# Channel_One.net
KiCad netlist of a schematic drawn in Altium Designer
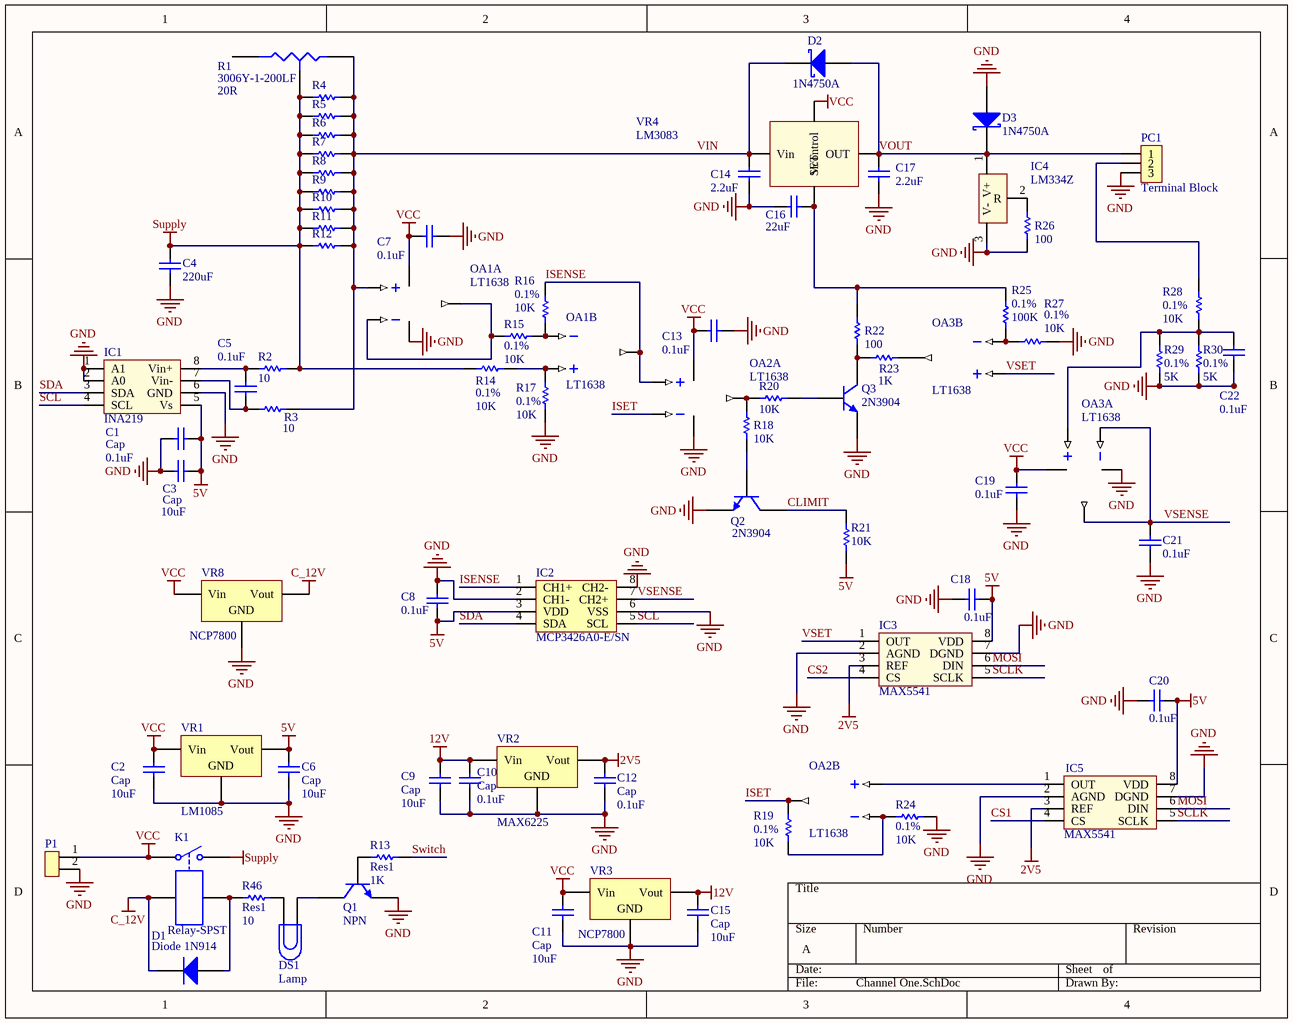
[diagram p0: Channel One.SchDoc]

(export (version "E")
  (design (tool "Eeschema 10.0.6"))
  (components
    (comp (ref "C1")
      (value "Cap")
      (footprint "RAD-0.1")
      (description "Capacitor")
      (fields (field (name "ALTIUM_VALUE") "0.1uF") (field (name "PUBLISHER") "Altium Limited"))
      (libsource (lib "Miscellaneous Devices") (part "Cap"))
    )
    (comp (ref "C2")
      (value "Cap")
      (footprint "RAD-0.2")
      (description "Capacitor")
      (fields (field (name "ALTIUM_VALUE") "10uF") (field (name "PUBLISHER") "Altium Limited"))
      (libsource (lib "Miscellaneous Devices") (part "Cap"))
    )
    (comp (ref "C3")
      (value "Cap")
      (footprint "RAD-0.2")
      (description "Capacitor")
      (fields (field (name "ALTIUM_VALUE") "10uF") (field (name "PUBLISHER") "Altium Limited"))
      (libsource (lib "Miscellaneous Devices") (part "Cap"))
    )
    (comp (ref "C4")
      (value "220uF")
      (footprint "RAD-0.2")
      (description "Capacitor")
      (fields (field (name "Comment") "Cap") (field (name "PUBLISHER") "Altium Limited"))
      (libsource (lib "Miscellaneous Devices") (part "Cap"))
    )
    (comp (ref "C5")
      (value "0.1uF")
      (footprint "RAD-0.1")
      (description "Capacitor")
      (fields (field (name "Comment") "Cap") (field (name "PUBLISHER") "Altium Limited"))
      (libsource (lib "Miscellaneous Devices") (part "Cap"))
    )
    (comp (ref "C6")
      (value "Cap")
      (footprint "RAD-0.2")
      (description "Capacitor")
      (fields (field (name "ALTIUM_VALUE") "10uF") (field (name "PUBLISHER") "Altium Limited"))
      (libsource (lib "Miscellaneous Devices") (part "Cap"))
    )
    (comp (ref "C7")
      (value "0.1uF")
      (footprint "RAD-0.1")
      (description "Capacitor")
      (fields (field (name "Comment") "Cap") (field (name "PUBLISHER") "Altium Limited"))
      (libsource (lib "Miscellaneous Devices") (part "Cap"))
    )
    (comp (ref "C8")
      (value "0.1uF")
      (footprint "RAD-0.1")
      (description "Capacitor")
      (fields (field (name "Comment") "Cap") (field (name "PUBLISHER") "Altium Limited"))
      (libsource (lib "Miscellaneous Devices") (part "Cap"))
    )
    (comp (ref "C9")
      (value "Cap")
      (footprint "RAD-0.2")
      (description "Capacitor")
      (fields (field (name "ALTIUM_VALUE") "10uF") (field (name "PUBLISHER") "Altium Limited"))
      (libsource (lib "Miscellaneous Devices") (part "Cap"))
    )
    (comp (ref "C10")
      (value "Cap")
      (footprint "RAD-0.1")
      (description "Capacitor")
      (fields (field (name "ALTIUM_VALUE") "0.1uF") (field (name "PUBLISHER") "Altium Limited"))
      (libsource (lib "Miscellaneous Devices") (part "Cap"))
    )
    (comp (ref "C11")
      (value "Cap")
      (footprint "RAD-0.2")
      (description "Capacitor")
      (fields (field (name "ALTIUM_VALUE") "10uF") (field (name "PUBLISHER") "Altium Limited"))
      (libsource (lib "Miscellaneous Devices") (part "Cap"))
    )
    (comp (ref "C12")
      (value "Cap")
      (footprint "RAD-0.1")
      (description "Capacitor")
      (fields (field (name "ALTIUM_VALUE") "0.1uF") (field (name "PUBLISHER") "Altium Limited"))
      (libsource (lib "Power Supply Library") (part "Cap"))
    )
    (comp (ref "C13")
      (value "0.1uF")
      (footprint "RAD-0.1")
      (description "Capacitor")
      (fields (field (name "Comment") "Cap") (field (name "PUBLISHER") "Altium Limited"))
      (libsource (lib "Miscellaneous Devices") (part "Cap"))
    )
    (comp (ref "C14")
      (value "2.2uF")
      (footprint "RAD-0.1")
      (description "Capacitor")
      (fields (field (name "Comment") "Cap") (field (name "PUBLISHER") "Altium Limited"))
      (libsource (lib "Miscellaneous Devices") (part "Cap"))
    )
    (comp (ref "C15")
      (value "Cap")
      (footprint "RAD-0.2")
      (description "Capacitor")
      (fields (field (name "ALTIUM_VALUE") "10uF") (field (name "PUBLISHER") "Altium Limited"))
      (libsource (lib "Miscellaneous Devices") (part "Cap"))
    )
    (comp (ref "C16")
      (value "22uF")
      (footprint "RAD-0.2")
      (description "Capacitor")
      (fields (field (name "Comment") "Cap") (field (name "PUBLISHER") "Altium Limited"))
      (libsource (lib "Miscellaneous Devices") (part "Cap"))
    )
    (comp (ref "C17")
      (value "2.2uF")
      (footprint "RAD-0.2")
      (description "Capacitor")
      (fields (field (name "Comment") "Cap") (field (name "PUBLISHER") "Altium Limited"))
      (libsource (lib "Miscellaneous Devices") (part "Cap"))
    )
    (comp (ref "C18")
      (value "0.1uF")
      (footprint "RAD-0.1")
      (description "Capacitor")
      (fields (field (name "Comment") "Cap") (field (name "PUBLISHER") "Altium Limited"))
      (libsource (lib "Miscellaneous Devices") (part "Cap"))
    )
    (comp (ref "C19")
      (value "0.1uF")
      (footprint "RAD-0.1")
      (description "Capacitor")
      (fields (field (name "Comment") "Cap") (field (name "PUBLISHER") "Altium Limited"))
      (libsource (lib "Miscellaneous Devices") (part "Cap"))
    )
    (comp (ref "C20")
      (value "0.1uF")
      (footprint "RAD-0.1")
      (description "Capacitor")
      (fields (field (name "Comment") "Cap") (field (name "PUBLISHER") "Altium Limited"))
      (libsource (lib "Miscellaneous Devices") (part "Cap"))
    )
    (comp (ref "C21")
      (value "0.1uF")
      (footprint "RAD-0.1")
      (description "Capacitor")
      (fields (field (name "Comment") "Cap") (field (name "PUBLISHER") "Altium Limited"))
      (libsource (lib "Miscellaneous Devices") (part "Cap"))
    )
    (comp (ref "C22")
      (value "0.1uF")
      (footprint "RAD-0.1")
      (description "Capacitor")
      (fields (field (name "Comment") "Cap") (field (name "PUBLISHER") "Altium Limited"))
      (libsource (lib "Miscellaneous Devices") (part "Cap"))
    )
    (comp (ref "D1")
      (value "Diode 1N914")
      (footprint "DO-35")
      (description "High Conductance Fast Diode")
      (fields (field (name "PUBLISHER") "Altium Limited"))
      (libsource (lib "Miscellaneous Devices") (part "Diode 1N914"))
    )
    (comp (ref "D2")
      (value "1N4750A")
      (footprint "DO-35")
      (description "Schottky Diode")
      (fields (field (name "PUBLISHER") "Altium Limited"))
      (libsource (lib "Miscellaneous Devices") (part "D Schottky"))
    )
    (comp (ref "D3")
      (value "1N4750A")
      (footprint "DO-35")
      (description "Schottky Diode")
      (fields (field (name "PUBLISHER") "Altium Limited"))
      (libsource (lib "Miscellaneous Devices") (part "D Schottky"))
    )
    (comp (ref "DS1")
      (value "Lamp")
      (footprint "PIN2")
      (description "Incandescent Bulb")
      (fields (field (name "PUBLISHER") "Altium Limited"))
      (libsource (lib "Miscellaneous Devices") (part "Lamp"))
    )
    (comp (ref "IC1")
      (value "INA219")
      (footprint "8-SO")
      (libsource (lib "Power Supply Library") (part "Current Sense"))
    )
    (comp (ref "IC2")
      (value "MCP3426A0-E/SN")
      (footprint "8-SO")
      (libsource (lib "Power Supply Library") (part "ADC"))
    )
    (comp (ref "IC3")
      (value "MAX5541")
      (footprint "8-SO")
      (libsource (lib "Power Supply Library") (part "DAC"))
    )
    (comp (ref "IC4")
      (value "LM334Z")
      (footprint "LM134")
      (libsource (lib "Power Supply Library") (part "Constant Current"))
    )
    (comp (ref "IC5")
      (value "MAX5541")
      (footprint "8-SO")
      (libsource (lib "Power Supply Library") (part "DAC"))
    )
    (comp (ref "K1")
      (value "Relay-SPST")
      (footprint "MODULE4")
      (description "Single-Pole Single-Throw Relay")
      (fields (field (name "PUBLISHER") "Altium Limited"))
      (libsource (lib "Power Supply Library") (part "Relay-SPST"))
    )
    (comp (ref "OA1")
      (value "LT1638")
      (footprint "8-DIP")
      (libsource (lib "Power Supply Library") (part "Operational Amp"))
    )
    (comp (ref "OA2")
      (value "LT1638")
      (footprint "8-DIP")
      (libsource (lib "Power Supply Library") (part "Operational Amp"))
    )
    (comp (ref "OA3")
      (value "LT1638")
      (footprint "8-DIP")
      (libsource (lib "Power Supply Library") (part "Operational Amp"))
    )
    (comp (ref "P1")
      (value "Power Connector")
      (footprint "Power Connector")
      (libsource (lib "Power Supply Library") (part "Power Connector"))
    )
    (comp (ref "PC1")
      (value "Terminal Block")
      (footprint "Terminal Block 3")
      (libsource (lib "Power Supply Library") (part "Terminal Block"))
    )
    (comp (ref "Q1")
      (value "NPN")
      (footprint "TO-226-AA")
      (description "NPN Bipolar Transistor")
      (fields (field (name "PUBLISHER") "Altium Limited"))
      (libsource (lib "Power Supply Library") (part "NPN"))
    )
    (comp (ref "Q2")
      (value "2N3904")
      (footprint "TO-226-AA")
      (description "NPN Bipolar Transistor")
      (fields (field (name "PUBLISHER") "Altium Limited"))
      (libsource (lib "Miscellaneous Devices") (part "NPN"))
    )
    (comp (ref "Q3")
      (value "2N3904")
      (footprint "TO-226-AA")
      (description "NPN Bipolar Transistor")
      (fields (field (name "PUBLISHER") "Altium Limited"))
      (libsource (lib "Miscellaneous Devices") (part "NPN"))
    )
    (comp (ref "R1")
      (value "3006Y-1-200LF")
      (footprint "VR3")
      (description "Tapped Resistor")
      (fields (field (name "ALTIUM_VALUE") "20R") (field (name "PUBLISHER") "Altium Limited"))
      (libsource (lib "Power Supply Library") (part "Res Tap"))
    )
    (comp (ref "R2")
      (value "10")
      (footprint "AXIAL-0.3")
      (description "Resistor")
      (fields (field (name "Comment") "Res1") (field (name "PUBLISHER") "Altium Limited"))
      (libsource (lib "Miscellaneous Devices") (part "Res1"))
    )
    (comp (ref "R3")
      (value "10")
      (footprint "AXIAL-0.3")
      (description "Resistor")
      (fields (field (name "Comment") "Res1") (field (name "PUBLISHER") "Altium Limited"))
      (libsource (lib "Miscellaneous Devices") (part "Res1"))
    )
    (comp (ref "R4")
      (value "Shunt")
      (footprint "AXIAL-0.3")
      (description "Resistor")
      (fields (field (name "PUBLISHER") "Altium Limited"))
      (libsource (lib "Miscellaneous Devices") (part "Res1"))
    )
    (comp (ref "R5")
      (value "Shunt")
      (footprint "AXIAL-0.3")
      (description "Resistor")
      (fields (field (name "PUBLISHER") "Altium Limited"))
      (libsource (lib "Miscellaneous Devices") (part "Res1"))
    )
    (comp (ref "R6")
      (value "Shunt")
      (footprint "AXIAL-0.3")
      (description "Resistor")
      (fields (field (name "PUBLISHER") "Altium Limited"))
      (libsource (lib "Miscellaneous Devices") (part "Res1"))
    )
    (comp (ref "R7")
      (value "Shunt")
      (footprint "AXIAL-0.3")
      (description "Resistor")
      (fields (field (name "PUBLISHER") "Altium Limited"))
      (libsource (lib "Miscellaneous Devices") (part "Res1"))
    )
    (comp (ref "R8")
      (value "Shunt")
      (footprint "AXIAL-0.3")
      (description "Resistor")
      (fields (field (name "PUBLISHER") "Altium Limited"))
      (libsource (lib "Miscellaneous Devices") (part "Res1"))
    )
    (comp (ref "R9")
      (value "Shunt")
      (footprint "AXIAL-0.3")
      (description "Resistor")
      (fields (field (name "PUBLISHER") "Altium Limited"))
      (libsource (lib "Miscellaneous Devices") (part "Res1"))
    )
    (comp (ref "R10")
      (value "Shunt")
      (footprint "AXIAL-0.3")
      (description "Resistor")
      (fields (field (name "PUBLISHER") "Altium Limited"))
      (libsource (lib "Miscellaneous Devices") (part "Res1"))
    )
    (comp (ref "R11")
      (value "Shunt")
      (footprint "AXIAL-0.3")
      (description "Resistor")
      (fields (field (name "PUBLISHER") "Altium Limited"))
      (libsource (lib "Miscellaneous Devices") (part "Res1"))
    )
    (comp (ref "R12")
      (value "Shunt")
      (footprint "AXIAL-0.3")
      (description "Resistor")
      (fields (field (name "PUBLISHER") "Altium Limited"))
      (libsource (lib "Miscellaneous Devices") (part "Res1"))
    )
    (comp (ref "R13")
      (value "Res1")
      (footprint "AXIAL-0.3")
      (description "Resistor")
      (fields (field (name "ALTIUM_VALUE") "1K") (field (name "PUBLISHER") "Altium Limited"))
      (libsource (lib "Power Supply Library") (part "Res1"))
    )
    (comp (ref "R14")
      (value "0.1%")
      (footprint "AXIAL-0.3")
      (description "Resistor")
      (fields (field (name "ALTIUM_VALUE") "10K") (field (name "PUBLISHER") "Altium Limited"))
      (libsource (lib "Miscellaneous Devices") (part "Res1"))
    )
    (comp (ref "R15")
      (value "0.1%")
      (footprint "AXIAL-0.3")
      (description "Resistor")
      (fields (field (name "ALTIUM_VALUE") "10K") (field (name "PUBLISHER") "Altium Limited"))
      (libsource (lib "Miscellaneous Devices") (part "Res1"))
    )
    (comp (ref "R16")
      (value "0.1%")
      (footprint "AXIAL-0.3")
      (description "Resistor")
      (fields (field (name "ALTIUM_VALUE") "10K") (field (name "PUBLISHER") "Altium Limited"))
      (libsource (lib "Miscellaneous Devices") (part "Res1"))
    )
    (comp (ref "R17")
      (value "0.1%")
      (footprint "AXIAL-0.3")
      (description "Resistor")
      (fields (field (name "ALTIUM_VALUE") "10K") (field (name "PUBLISHER") "Altium Limited"))
      (libsource (lib "Miscellaneous Devices") (part "Res1"))
    )
    (comp (ref "R18")
      (value "10K")
      (footprint "AXIAL-0.3")
      (description "Resistor")
      (fields (field (name "Comment") "Res") (field (name "PUBLISHER") "Altium Limited"))
      (libsource (lib "Miscellaneous Devices") (part "Res1"))
    )
    (comp (ref "R19")
      (value "0.1%")
      (footprint "AXIAL-0.3")
      (description "Resistor")
      (fields (field (name "ALTIUM_VALUE") "10K") (field (name "PUBLISHER") "Altium Limited"))
      (libsource (lib "Miscellaneous Devices") (part "Res1"))
    )
    (comp (ref "R20")
      (value "10K")
      (footprint "AXIAL-0.3")
      (description "Resistor")
      (fields (field (name "Comment") "Res") (field (name "PUBLISHER") "Altium Limited"))
      (libsource (lib "Miscellaneous Devices") (part "Res1"))
    )
    (comp (ref "R21")
      (value "10K")
      (footprint "AXIAL-0.3")
      (description "Resistor")
      (fields (field (name "Comment") "Res1") (field (name "PUBLISHER") "Altium Limited"))
      (libsource (lib "Miscellaneous Devices") (part "Res1"))
    )
    (comp (ref "R22")
      (value "100")
      (footprint "AXIAL-0.3")
      (description "Resistor")
      (fields (field (name "Comment") "Res") (field (name "PUBLISHER") "Altium Limited"))
      (libsource (lib "Miscellaneous Devices") (part "Res1"))
    )
    (comp (ref "R23")
      (value "1K")
      (footprint "AXIAL-0.3")
      (description "Resistor")
      (fields (field (name "Comment") "Res") (field (name "PUBLISHER") "Altium Limited"))
      (libsource (lib "Miscellaneous Devices") (part "Res1"))
    )
    (comp (ref "R24")
      (value "0.1%")
      (footprint "AXIAL-0.3")
      (description "Resistor")
      (fields (field (name "ALTIUM_VALUE") "10K") (field (name "PUBLISHER") "Altium Limited"))
      (libsource (lib "Miscellaneous Devices") (part "Res1"))
    )
    (comp (ref "R25")
      (value "0.1%")
      (footprint "AXIAL-0.3")
      (description "Resistor")
      (fields (field (name "ALTIUM_VALUE") "100K") (field (name "PUBLISHER") "Altium Limited"))
      (libsource (lib "Miscellaneous Devices") (part "Res1"))
    )
    (comp (ref "R26")
      (value "100")
      (footprint "AXIAL-0.3")
      (description "Resistor")
      (fields (field (name "Comment") "Res") (field (name "PUBLISHER") "Altium Limited"))
      (libsource (lib "Miscellaneous Devices") (part "Res1"))
    )
    (comp (ref "R27")
      (value "0.1%")
      (footprint "AXIAL-0.3")
      (description "Resistor")
      (fields (field (name "ALTIUM_VALUE") "10K") (field (name "PUBLISHER") "Altium Limited"))
      (libsource (lib "Miscellaneous Devices") (part "Res1"))
    )
    (comp (ref "R28")
      (value "0.1%")
      (footprint "AXIAL-0.3")
      (description "Resistor")
      (fields (field (name "ALTIUM_VALUE") "10K") (field (name "PUBLISHER") "Altium Limited"))
      (libsource (lib "Miscellaneous Devices") (part "Res1"))
    )
    (comp (ref "R29")
      (value "0.1%")
      (footprint "AXIAL-0.3")
      (description "Resistor")
      (fields (field (name "ALTIUM_VALUE") "5K") (field (name "PUBLISHER") "Altium Limited"))
      (libsource (lib "Miscellaneous Devices") (part "Res1"))
    )
    (comp (ref "R30")
      (value "0.1%")
      (footprint "AXIAL-0.3")
      (description "Resistor")
      (fields (field (name "ALTIUM_VALUE") "5K") (field (name "PUBLISHER") "Altium Limited"))
      (libsource (lib "Miscellaneous Devices") (part "Res1"))
    )
    (comp (ref "R46")
      (value "Res1")
      (footprint "AXIAL-0.3")
      (description "Resistor")
      (fields (field (name "ALTIUM_VALUE") "10") (field (name "PUBLISHER") "Altium Limited"))
      (libsource (lib "Power Supply Library") (part "Res1"))
    )
    (comp (ref "VR1")
      (value "LM1085")
      (footprint "TO220")
      (libsource (lib "Power Supply Library") (part "Voltage Regulator 5V"))
    )
    (comp (ref "VR2")
      (value "MAX6225")
      (footprint "8-DIP")
      (libsource (lib "Power Supply Library") (part "Voltage Reference 2.5V"))
    )
    (comp (ref "VR3")
      (value "NCP7800")
      (footprint "TO220")
      (libsource (lib "Power Supply Library") (part "Voltage Regulator 12V"))
    )
    (comp (ref "VR4")
      (value "LM3083")
      (footprint "LT3083")
      (libsource (lib "Power Supply Library") (part "Adjustable Regulator"))
    )
    (comp (ref "VR8")
      (value "NCP7800")
      (footprint "TO220")
      (libsource (lib "Power Supply Library") (part "Voltage Regulator 12V"))
    )
  )
  (nets
    (net (code "1") (name "/CLIMIT") (class "Default")
      (node (ref "Q2") (pin "1") (pinfunction "C_1") (pintype "passive"))
      (node (ref "R21") (pin "2") (pinfunction "2_2") (pintype "passive"))
    )
    (net (code "2") (name "/CS1") (class "Default")
      (node (ref "IC5") (pin "4") (pinfunction "CS_4") (pintype "passive"))
    )
    (net (code "3") (name "/CS2") (class "Default")
      (node (ref "IC3") (pin "4") (pinfunction "CS_4") (pintype "passive"))
    )
    (net (code "4") (name "/ISENSE") (class "Default")
      (node (ref "IC2") (pin "1") (pinfunction "CH1+_1") (pintype "passive"))
      (node (ref "OA1") (pin "7") (pinfunction "OUTB_7") (pintype "output"))
      (node (ref "OA2") (pin "3") (pinfunction "+INA_3") (pintype "input"))
      (node (ref "R16") (pin "2") (pinfunction "2_2") (pintype "passive"))
    )
    (net (code "5") (name "/ISET") (class "Default")
      (node (ref "OA2") (pin "2") (pinfunction "-INA_2") (pintype "input"))
      (node (ref "OA2") (pin "7") (pinfunction "OUTB_7") (pintype "output"))
      (node (ref "R19") (pin "1") (pinfunction "1_1") (pintype "passive"))
    )
    (net (code "6") (name "/MOSI") (class "Default")
      (node (ref "IC3") (pin "6") (pinfunction "DIN_6") (pintype "passive"))
      (node (ref "IC5") (pin "6") (pinfunction "DIN_6") (pintype "passive"))
    )
    (net (code "7") (name "/SCL") (class "Default")
      (node (ref "IC1") (pin "4") (pinfunction "SCL_4") (pintype "passive"))
      (node (ref "IC2") (pin "5") (pinfunction "SCL_5") (pintype "passive"))
    )
    (net (code "8") (name "/SCLK") (class "Default")
      (node (ref "IC3") (pin "5") (pinfunction "SCLK_5") (pintype "passive"))
      (node (ref "IC5") (pin "5") (pinfunction "SCLK_5") (pintype "passive"))
    )
    (net (code "9") (name "/SDA") (class "Default")
      (node (ref "IC1") (pin "3") (pinfunction "SDA_3") (pintype "passive"))
      (node (ref "IC2") (pin "4") (pinfunction "SDA_4") (pintype "passive"))
    )
    (net (code "10") (name "/Switch") (class "Default")
      (node (ref "R13") (pin "1") (pinfunction "1_1") (pintype "passive"))
    )
    (net (code "11") (name "/VIN") (class "Default")
      (node (ref "C14") (pin "2") (pinfunction "2_2") (pintype "passive"))
      (node (ref "D2") (pin "2") (pinfunction "K_2") (pintype "passive"))
      (node (ref "OA1") (pin "3") (pinfunction "+INA_3") (pintype "input"))
      (node (ref "R1") (pin "1") (pinfunction "A_1") (pintype "passive"))
      (node (ref "R10") (pin "2") (pinfunction "2_2") (pintype "passive"))
      (node (ref "R11") (pin "2") (pinfunction "2_2") (pintype "passive"))
      (node (ref "R12") (pin "2") (pinfunction "2_2") (pintype "passive"))
      (node (ref "R3") (pin "2") (pinfunction "2_2") (pintype "passive"))
      (node (ref "R4") (pin "2") (pinfunction "2_2") (pintype "passive"))
      (node (ref "R5") (pin "2") (pinfunction "2_2") (pintype "passive"))
      (node (ref "R6") (pin "2") (pinfunction "2_2") (pintype "passive"))
      (node (ref "R7") (pin "2") (pinfunction "2_2") (pintype "passive"))
      (node (ref "R8") (pin "2") (pinfunction "2_2") (pintype "passive"))
      (node (ref "R9") (pin "2") (pinfunction "2_2") (pintype "passive"))
      (node (ref "VR4") (pin "5") (pinfunction "Vin_5") (pintype "passive"))
    )
    (net (code "12") (name "/VOUT") (class "Default")
      (node (ref "C17") (pin "2") (pinfunction "2_2") (pintype "passive"))
      (node (ref "D2") (pin "1") (pinfunction "A_1") (pintype "passive"))
      (node (ref "D3") (pin "2") (pinfunction "K_2") (pintype "passive"))
      (node (ref "IC4") (pin "1") (pinfunction "V+_1") (pintype "passive"))
      (node (ref "PC1") (pin "1") (pinfunction "1_1") (pintype "passive"))
      (node (ref "VR4") (pin "3") (pinfunction "OUT_3") (pintype "passive"))
    )
    (net (code "13") (name "/VSENSE") (class "Default")
      (node (ref "C21") (pin "1") (pinfunction "1_1") (pintype "passive"))
      (node (ref "IC2") (pin "7") (pinfunction "CH2+_7") (pintype "passive"))
      (node (ref "OA3") (pin "1") (pinfunction "OUTA_1") (pintype "output"))
      (node (ref "OA3") (pin "2") (pinfunction "-INA_2") (pintype "input"))
    )
    (net (code "14") (name "/VSET") (class "Default")
      (node (ref "IC3") (pin "1") (pinfunction "OUT_1") (pintype "passive"))
      (node (ref "OA3") (pin "5") (pinfunction "+INB_5") (pintype "input"))
    )
    (net (code "15") (name "2V5") (class "Default")
      (node (ref "C12") (pin "2") (pinfunction "2_2") (pintype "passive"))
      (node (ref "IC3") (pin "3") (pinfunction "REF_3") (pintype "passive"))
      (node (ref "IC5") (pin "3") (pinfunction "REF_3") (pintype "passive"))
      (node (ref "VR2") (pin "6") (pinfunction "Vout_6") (pintype "passive"))
    )
    (net (code "16") (name "5V") (class "Default")
      (node (ref "C1") (pin "2") (pinfunction "2_2") (pintype "passive"))
      (node (ref "C18") (pin "2") (pinfunction "2_2") (pintype "passive"))
      (node (ref "C20") (pin "2") (pinfunction "2_2") (pintype "passive"))
      (node (ref "C3") (pin "2") (pinfunction "2_2") (pintype "passive"))
      (node (ref "C6") (pin "2") (pinfunction "2_2") (pintype "passive"))
      (node (ref "C8") (pin "1") (pinfunction "1_1") (pintype "passive"))
      (node (ref "IC1") (pin "5") (pinfunction "Vs_5") (pintype "passive"))
      (node (ref "IC2") (pin "3") (pinfunction "VDD_3") (pintype "passive"))
      (node (ref "IC3") (pin "8") (pinfunction "VDD_8") (pintype "passive"))
      (node (ref "IC5") (pin "8") (pinfunction "VDD_8") (pintype "passive"))
      (node (ref "R21") (pin "1") (pinfunction "1_1") (pintype "passive"))
      (node (ref "VR1") (pin "3") (pinfunction "Vout_3") (pintype "passive"))
    )
    (net (code "17") (name "12V") (class "Default")
      (node (ref "C10") (pin "2") (pinfunction "2_2") (pintype "passive"))
      (node (ref "C15") (pin "2") (pinfunction "2_2") (pintype "passive"))
      (node (ref "C9") (pin "2") (pinfunction "2_2") (pintype "passive"))
      (node (ref "VR2") (pin "2") (pinfunction "Vin_2") (pintype "passive"))
      (node (ref "VR3") (pin "3") (pinfunction "Vout_3") (pintype "passive"))
    )
    (net (code "18") (name "C_12V") (class "Default")
      (node (ref "D1") (pin "2") (pinfunction "K_2") (pintype "passive"))
      (node (ref "K1") (pin "3") (pinfunction "3_3") (pintype "passive"))
      (node (ref "VR8") (pin "3") (pinfunction "Vout_3") (pintype "passive"))
    )
    (net (code "19") (name "GND") (class "Default")
      (node (ref "C1") (pin "1") (pinfunction "1_1") (pintype "passive"))
      (node (ref "C10") (pin "1") (pinfunction "1_1") (pintype "passive"))
      (node (ref "C11") (pin "1") (pinfunction "1_1") (pintype "passive"))
      (node (ref "C12") (pin "1") (pinfunction "1_1") (pintype "passive"))
      (node (ref "C13") (pin "2") (pinfunction "2_2") (pintype "passive"))
      (node (ref "C14") (pin "1") (pinfunction "1_1") (pintype "passive"))
      (node (ref "C15") (pin "1") (pinfunction "1_1") (pintype "passive"))
      (node (ref "C16") (pin "2") (pinfunction "2_2") (pintype "passive"))
      (node (ref "C17") (pin "1") (pinfunction "1_1") (pintype "passive"))
      (node (ref "C18") (pin "1") (pinfunction "1_1") (pintype "passive"))
      (node (ref "C19") (pin "1") (pinfunction "1_1") (pintype "passive"))
      (node (ref "C2") (pin "1") (pinfunction "1_1") (pintype "passive"))
      (node (ref "C20") (pin "1") (pinfunction "1_1") (pintype "passive"))
      (node (ref "C21") (pin "2") (pinfunction "2_2") (pintype "passive"))
      (node (ref "C22") (pin "2") (pinfunction "2_2") (pintype "passive"))
      (node (ref "C3") (pin "1") (pinfunction "1_1") (pintype "passive"))
      (node (ref "C4") (pin "1") (pinfunction "1_1") (pintype "passive"))
      (node (ref "C6") (pin "1") (pinfunction "1_1") (pintype "passive"))
      (node (ref "C7") (pin "2") (pinfunction "2_2") (pintype "passive"))
      (node (ref "C8") (pin "2") (pinfunction "2_2") (pintype "passive"))
      (node (ref "C9") (pin "1") (pinfunction "1_1") (pintype "passive"))
      (node (ref "D3") (pin "1") (pinfunction "A_1") (pintype "passive"))
      (node (ref "IC1") (pin "1") (pinfunction "A1_1") (pintype "passive"))
      (node (ref "IC1") (pin "2") (pinfunction "A0_2") (pintype "passive"))
      (node (ref "IC1") (pin "6") (pinfunction "GND_6") (pintype "passive"))
      (node (ref "IC2") (pin "2") (pinfunction "CH1-_2") (pintype "passive"))
      (node (ref "IC2") (pin "6") (pinfunction "VSS_6") (pintype "passive"))
      (node (ref "IC2") (pin "8") (pinfunction "CH2-_8") (pintype "passive"))
      (node (ref "IC3") (pin "2") (pinfunction "AGND_2") (pintype "passive"))
      (node (ref "IC3") (pin "7") (pinfunction "DGND_7") (pintype "passive"))
      (node (ref "IC4") (pin "3") (pinfunction "V-_3") (pintype "passive"))
      (node (ref "IC5") (pin "2") (pinfunction "AGND_2") (pintype "passive"))
      (node (ref "IC5") (pin "7") (pinfunction "DGND_7") (pintype "passive"))
      (node (ref "OA1") (pin "4") (pinfunction "V-_4") (pintype "passive"))
      (node (ref "OA2") (pin "4") (pinfunction "V-_4") (pintype "passive"))
      (node (ref "OA3") (pin "4") (pinfunction "V-_4") (pintype "passive"))
      (node (ref "P1") (pin "2") (pintype "passive"))
      (node (ref "PC1") (pin "3") (pinfunction "3_3") (pintype "passive"))
      (node (ref "Q1") (pin "3") (pinfunction "E_3") (pintype "passive"))
      (node (ref "Q2") (pin "3") (pinfunction "E_3") (pintype "passive"))
      (node (ref "Q3") (pin "3") (pinfunction "E_3") (pintype "passive"))
      (node (ref "R17") (pin "1") (pinfunction "1_1") (pintype "passive"))
      (node (ref "R24") (pin "2") (pinfunction "2_2") (pintype "passive"))
      (node (ref "R26") (pin "2") (pinfunction "2_2") (pintype "passive"))
      (node (ref "R27") (pin "2") (pinfunction "2_2") (pintype "passive"))
      (node (ref "R29") (pin "1") (pinfunction "1_1") (pintype "passive"))
      (node (ref "R30") (pin "1") (pinfunction "1_1") (pintype "passive"))
      (node (ref "VR1") (pin "2") (pinfunction "GND_2") (pintype "passive"))
      (node (ref "VR2") (pin "4") (pinfunction "GND_4") (pintype "passive"))
      (node (ref "VR3") (pin "2") (pinfunction "GND_2") (pintype "passive"))
      (node (ref "VR8") (pin "2") (pinfunction "GND_2") (pintype "passive"))
    )
    (net (code "20") (name "Net-(D1-A)") (class "Default")
      (node (ref "D1") (pin "1") (pinfunction "A_1") (pintype "passive"))
      (node (ref "K1") (pin "4") (pinfunction "4_4") (pintype "passive"))
      (node (ref "R46") (pin "2") (pinfunction "2_2") (pintype "passive"))
    )
    (net (code "21") (name "Net-(DS1-Pad2)") (class "Default")
      (node (ref "DS1") (pin "2") (pinfunction "2_2") (pintype "passive"))
      (node (ref "R46") (pin "1") (pinfunction "1_1") (pintype "passive"))
    )
    (net (code "22") (name "Net-(IC1-Vin+)") (class "Default")
      (node (ref "C5") (pin "2") (pinfunction "2_2") (pintype "passive"))
      (node (ref "IC1") (pin "8") (pinfunction "Vin+_8") (pintype "passive"))
      (node (ref "R2") (pin "2") (pinfunction "2_2") (pintype "passive"))
    )
    (net (code "23") (name "Net-(IC1-Vin-)") (class "Default")
      (node (ref "C5") (pin "1") (pinfunction "1_1") (pintype "passive"))
      (node (ref "IC1") (pin "7") (pinfunction "Vin-_7") (pintype "passive"))
      (node (ref "R3") (pin "1") (pinfunction "1_1") (pintype "passive"))
    )
    (net (code "24") (name "Net-(IC4-R)") (class "Default")
      (node (ref "IC4") (pin "2") (pinfunction "R_2") (pintype "passive"))
      (node (ref "R26") (pin "1") (pinfunction "1_1") (pintype "passive"))
    )
    (net (code "25") (name "Net-(IC5-OUT)") (class "Default")
      (node (ref "IC5") (pin "1") (pinfunction "OUT_1") (pintype "passive"))
      (node (ref "OA2") (pin "5") (pinfunction "+INB_5") (pintype "input"))
    )
    (net (code "26") (name "Net-(OA1A--INA)") (class "Default")
      (node (ref "OA1") (pin "1") (pinfunction "OUTA_1") (pintype "output"))
      (node (ref "OA1") (pin "2") (pinfunction "-INA_2") (pintype "input"))
      (node (ref "R15") (pin "1") (pinfunction "1_1") (pintype "passive"))
    )
    (net (code "27") (name "Net-(OA1B-+INB)") (class "Default")
      (node (ref "OA1") (pin "5") (pinfunction "+INB_5") (pintype "input"))
      (node (ref "R14") (pin "2") (pinfunction "2_2") (pintype "passive"))
      (node (ref "R17") (pin "2") (pinfunction "2_2") (pintype "passive"))
    )
    (net (code "28") (name "Net-(OA1B--INB)") (class "Default")
      (node (ref "OA1") (pin "6") (pinfunction "-INB_6") (pintype "input"))
      (node (ref "R15") (pin "2") (pinfunction "2_2") (pintype "passive"))
      (node (ref "R16") (pin "1") (pinfunction "1_1") (pintype "passive"))
    )
    (net (code "29") (name "Net-(OA2A-OUTA)") (class "Default")
      (node (ref "OA2") (pin "1") (pinfunction "OUTA_1") (pintype "output"))
      (node (ref "R18") (pin "1") (pinfunction "1_1") (pintype "passive"))
      (node (ref "R20") (pin "2") (pinfunction "2_2") (pintype "passive"))
    )
    (net (code "30") (name "Net-(OA2B--INB)") (class "Default")
      (node (ref "OA2") (pin "6") (pinfunction "-INB_6") (pintype "input"))
      (node (ref "R19") (pin "2") (pinfunction "2_2") (pintype "passive"))
      (node (ref "R24") (pin "1") (pinfunction "1_1") (pintype "passive"))
    )
    (net (code "31") (name "Net-(OA3A-+INA)") (class "Default")
      (node (ref "C22") (pin "1") (pinfunction "1_1") (pintype "passive"))
      (node (ref "OA3") (pin "3") (pinfunction "+INA_3") (pintype "input"))
      (node (ref "R28") (pin "1") (pinfunction "1_1") (pintype "passive"))
      (node (ref "R29") (pin "2") (pinfunction "2_2") (pintype "passive"))
      (node (ref "R30") (pin "2") (pinfunction "2_2") (pintype "passive"))
    )
    (net (code "32") (name "Net-(OA3B--INB)") (class "Default")
      (node (ref "OA3") (pin "6") (pinfunction "-INB_6") (pintype "input"))
      (node (ref "R25") (pin "2") (pinfunction "2_2") (pintype "passive"))
      (node (ref "R27") (pin "1") (pinfunction "1_1") (pintype "passive"))
    )
    (net (code "33") (name "Net-(OA3B-OUTB)") (class "Default")
      (node (ref "OA3") (pin "7") (pinfunction "OUTB_7") (pintype "output"))
      (node (ref "R23") (pin "2") (pinfunction "2_2") (pintype "passive"))
    )
    (net (code "34") (name "Net-(PC1-Pad2)") (class "Default")
      (node (ref "PC1") (pin "2") (pinfunction "2_2") (pintype "passive"))
      (node (ref "R28") (pin "2") (pinfunction "2_2") (pintype "passive"))
    )
    (net (code "35") (name "Net-(Q1-B)") (class "Default")
      (node (ref "Q1") (pin "2") (pinfunction "B_2") (pintype "passive"))
      (node (ref "R13") (pin "2") (pinfunction "2_2") (pintype "passive"))
    )
    (net (code "36") (name "Net-(Q1-C)") (class "Default")
      (node (ref "DS1") (pin "1") (pinfunction "1_1") (pintype "passive"))
      (node (ref "Q1") (pin "1") (pinfunction "C_1") (pintype "passive"))
    )
    (net (code "37") (name "Net-(Q2-B)") (class "Default")
      (node (ref "Q2") (pin "2") (pinfunction "B_2") (pintype "passive"))
      (node (ref "R18") (pin "2") (pinfunction "2_2") (pintype "passive"))
    )
    (net (code "38") (name "Net-(Q3-B)") (class "Default")
      (node (ref "Q3") (pin "2") (pinfunction "B_2") (pintype "passive"))
      (node (ref "R20") (pin "1") (pinfunction "1_1") (pintype "passive"))
    )
    (net (code "39") (name "Net-(Q3-C)") (class "Default")
      (node (ref "Q3") (pin "1") (pinfunction "C_1") (pintype "passive"))
      (node (ref "R22") (pin "2") (pinfunction "2_2") (pintype "passive"))
      (node (ref "R23") (pin "1") (pinfunction "1_1") (pintype "passive"))
    )
    (net (code "40") (name "Net-(VR4-SET)") (class "Default")
      (node (ref "C16") (pin "1") (pinfunction "1_1") (pintype "passive"))
      (node (ref "R22") (pin "1") (pinfunction "1_1") (pintype "passive"))
      (node (ref "R25") (pin "1") (pinfunction "1_1") (pintype "passive"))
      (node (ref "VR4") (pin "2") (pinfunction "SET_2") (pintype "passive"))
    )
    (net (code "41") (name "Supply") (class "Default")
      (node (ref "C4") (pin "2") (pinfunction "2_2") (pintype "passive"))
      (node (ref "K1") (pin "2") (pinfunction "2_2") (pintype "passive"))
      (node (ref "R1") (pin "3") (pinfunction "TAP_3") (pintype "passive"))
      (node (ref "R10") (pin "1") (pinfunction "1_1") (pintype "passive"))
      (node (ref "R11") (pin "1") (pinfunction "1_1") (pintype "passive"))
      (node (ref "R12") (pin "1") (pinfunction "1_1") (pintype "passive"))
      (node (ref "R14") (pin "1") (pinfunction "1_1") (pintype "passive"))
      (node (ref "R2") (pin "1") (pinfunction "1_1") (pintype "passive"))
      (node (ref "R4") (pin "1") (pinfunction "1_1") (pintype "passive"))
      (node (ref "R5") (pin "1") (pinfunction "1_1") (pintype "passive"))
      (node (ref "R6") (pin "1") (pinfunction "1_1") (pintype "passive"))
      (node (ref "R7") (pin "1") (pinfunction "1_1") (pintype "passive"))
      (node (ref "R8") (pin "1") (pinfunction "1_1") (pintype "passive"))
      (node (ref "R9") (pin "1") (pinfunction "1_1") (pintype "passive"))
    )
    (net (code "42") (name "VCC") (class "Default")
      (node (ref "C11") (pin "2") (pinfunction "2_2") (pintype "passive"))
      (node (ref "C13") (pin "1") (pinfunction "1_1") (pintype "passive"))
      (node (ref "C19") (pin "2") (pinfunction "2_2") (pintype "passive"))
      (node (ref "C2") (pin "2") (pinfunction "2_2") (pintype "passive"))
      (node (ref "C7") (pin "1") (pinfunction "1_1") (pintype "passive"))
      (node (ref "K1") (pin "1") (pinfunction "1_1") (pintype "passive"))
      (node (ref "OA1") (pin "8") (pinfunction "V+_8") (pintype "passive"))
      (node (ref "OA2") (pin "8") (pinfunction "V+_8") (pintype "passive"))
      (node (ref "OA3") (pin "8") (pinfunction "V+_8") (pintype "passive"))
      (node (ref "P1") (pin "1") (pintype "passive"))
      (node (ref "VR1") (pin "1") (pinfunction "Vin_1") (pintype "passive"))
      (node (ref "VR3") (pin "1") (pinfunction "Vin_1") (pintype "passive"))
      (node (ref "VR4") (pin "4") (pinfunction "Vcontrol_4") (pintype "passive"))
      (node (ref "VR8") (pin "1") (pinfunction "Vin_1") (pintype "passive"))
    )
    (net (code "43") (name "unconnected-(R1-B-Pad2)") (class "Default")
      (node (ref "R1") (pin "2") (pinfunction "B_2") (pintype "passive"))
    )
  )
)
